# 03_-_CIRCUITO.net
KiCad netlist of a schematic drawn in Altium Designer
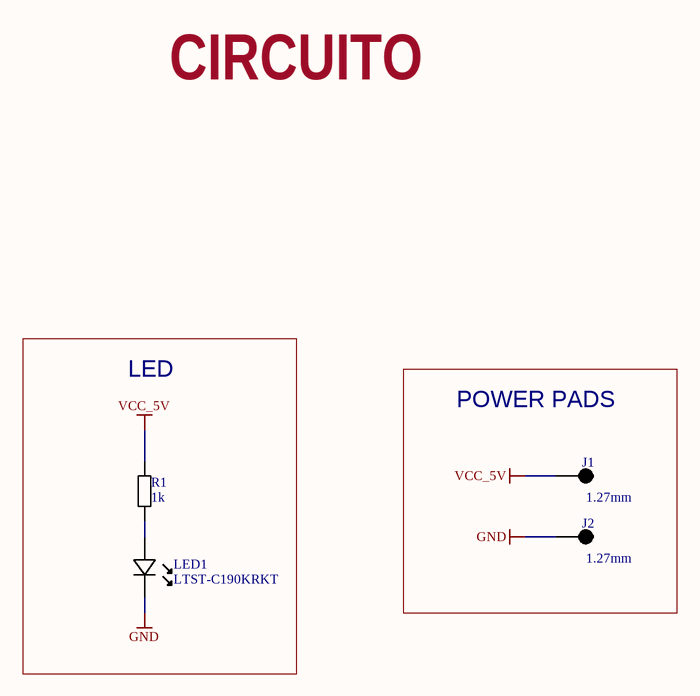
[diagram p0: [03] - CIRCUITO.SchDoc]

(export (version "E")
  (design (tool "Eeschema 10.0.6"))
  (components
    (comp (ref "J1")
      (value "1.27mm")
      (footprint "SOLDER PAD - 1.27mm")
      (description "SOLDER_PAD_ROUND_127MM")
      (libsource (lib "tiny_pendant") (part "SOLDER_PAD_R_127MM"))
    )
    (comp (ref "J2")
      (value "1.27mm")
      (footprint "SOLDER PAD - 1.27mm")
      (description "SOLDER_PAD_ROUND_127MM")
      (libsource (lib "tiny_pendant") (part "SOLDER_PAD_R_127MM"))
    )
    (comp (ref "LED1")
      (value "RED")
      (footprint "LED-0603-RED")
      (description "LED RED CLEAR 0603 SMD")
      (fields
        (field (name "MANUFACTURER") "Lite-On Inc.")
        (field (name "MANUFACTURER PART NUMBER") "LTST-C190KRKT")
      )
      (libsource (lib "tiny_pendant") (part "LED RED CLEAR 0603 SMD"))
    )
    (comp (ref "R1")
      (value "1k")
      (footprint "RESC1608X06N")
      (description "RES SMD 1K OHM 1% 1/10W 0603")
      (fields
        (field (name "MANUFACTURER") "Yageo")
        (field (name "MANUFACTURER PART NUMBER") "RC0603JR-071KL")
      )
      (libsource (lib "tiny_pendant") (part "RES 1K 0603 1%"))
    )
  )
  (nets
    (net (code "1") (name "GND") (class "Default")
      (node (ref "J2") (pin "1") (pinfunction "1_1") (pintype "passive"))
      (node (ref "LED1") (pin "K") (pinfunction "K_K") (pintype "passive"))
    )
    (net (code "2") (name "Net-(LED1-PadA)") (class "Default")
      (node (ref "LED1") (pin "A") (pinfunction "A_A") (pintype "passive"))
      (node (ref "R1") (pin "1") (pinfunction "1_1") (pintype "passive"))
    )
    (net (code "3") (name "VCC_5V") (class "Default")
      (node (ref "J1") (pin "1") (pinfunction "1_1") (pintype "passive"))
      (node (ref "R1") (pin "2") (pinfunction "2_2") (pintype "passive"))
    )
  )
)
